# hv_control.net
KiCad netlist of a schematic drawn in Altium Designer
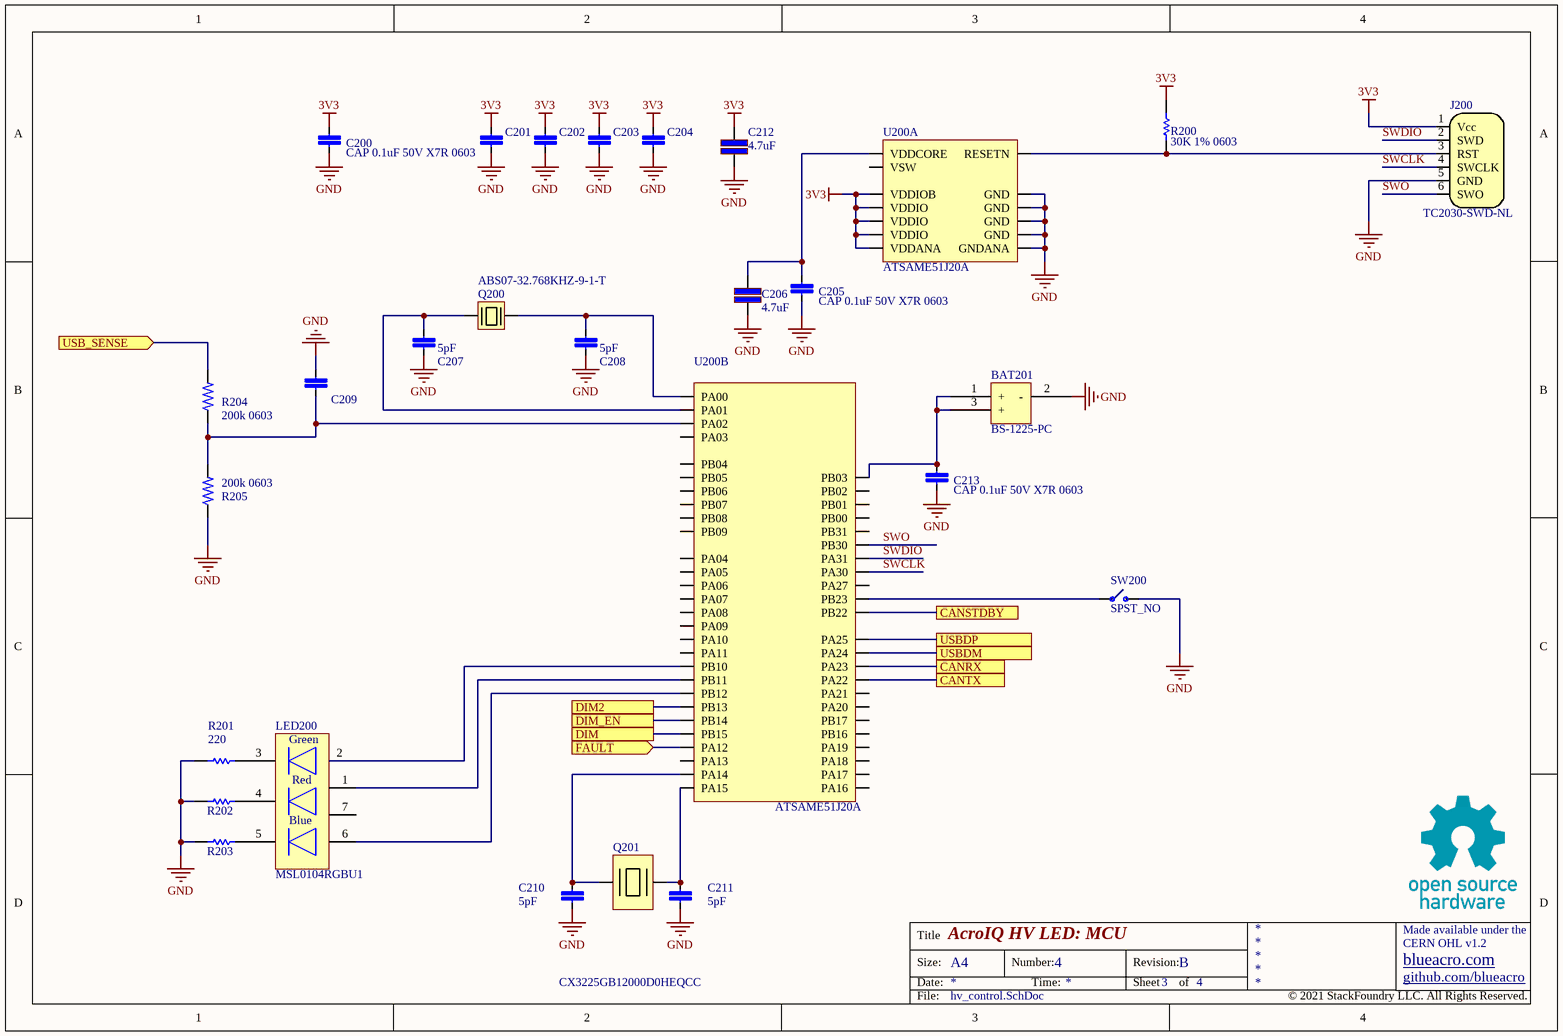
[diagram p0: hv_control.SchDoc]

(export (version "E")
  (design (tool "Eeschema 10.0.6"))
  (components
    (comp (ref "BAT201")
      (value "BS-1225-PC")
      (footprint "BS-1225-PC-Footprint-1")
      (description "BATTERY HOLDER COIN PC PIN")
      (libsource (lib "StackFoundry LLC") (part "BS-1225-PC"))
    )
    (comp (ref "C200")
      (value "CAP 0.1uF 50V X7R 0603")
      (footprint "FP-CL10-IPC_B")
      (description "Cap Ceramic 0.1uF 50V X7R 20% SMD 0603 125C Paper T/R")
      (libsource (lib "StackFoundry LLC") (part "C-EU"))
    )
    (comp (ref "C201")
      (value "CAP 0.1uF 50V X7R 0603")
      (footprint "FP-CL10-IPC_B")
      (description "Cap Ceramic 0.1uF 50V X7R 20% SMD 0603 125C Paper T/R")
      (libsource (lib "StackFoundry LLC") (part "C-EU"))
    )
    (comp (ref "C202")
      (value "CAP 0.1uF 50V X7R 0603")
      (footprint "FP-CL10-IPC_B")
      (description "Cap Ceramic 0.1uF 50V X7R 20% SMD 0603 125C Paper T/R")
      (libsource (lib "StackFoundry LLC") (part "C-EU"))
    )
    (comp (ref "C203")
      (value "CAP 0.1uF 50V X7R 0603")
      (footprint "FP-CL10-IPC_B")
      (description "Cap Ceramic 0.1uF 50V X7R 20% SMD 0603 125C Paper T/R")
      (libsource (lib "StackFoundry LLC") (part "C-EU"))
    )
    (comp (ref "C204")
      (value "CAP 0.1uF 50V X7R 0603")
      (footprint "FP-CL10-IPC_B")
      (description "Cap Ceramic 0.1uF 50V X7R 20% SMD 0603 125C Paper T/R")
      (libsource (lib "StackFoundry LLC") (part "C-EU"))
    )
    (comp (ref "C205")
      (value "CAP 0.1uF 50V X7R 0603")
      (footprint "FP-CL10-IPC_B")
      (description "Cap Ceramic 0.1uF 50V X7R 20% SMD 0603 125C Paper T/R")
      (libsource (lib "StackFoundry LLC") (part "C-EU"))
    )
    (comp (ref "C206")
      (value "4.7uF")
      (footprint "CAPC3225X20N")
      (description "CAP CER 4.7UF 50V X7R 1210")
      (fields (field (name "TOLERANCE") "10%") (field (name "VOLTAGE") "50V"))
      (libsource (lib "StackFoundry LLC") (part "4.7uF"))
    )
    (comp (ref "C207")
      (value "5pF")
      (footprint "FP-CL10-IPC_B")
      (description "CAP CER 5PF 50V C0G/NP0 0603")
      (libsource (lib "StackFoundry LLC") (part "C-EU"))
    )
    (comp (ref "C208")
      (value "5pF")
      (footprint "FP-CL10-IPC_B")
      (description "CAP CER 5PF 50V C0G/NP0 0603")
      (libsource (lib "StackFoundry LLC") (part "C-EU"))
    )
    (comp (ref "C209")
      (value "CAP 0.022uF 50V X7R 0603")
      (footprint "FP-CL10-IPC_B")
      (libsource (lib "StackFoundry LLC") (part "C-EU"))
    )
    (comp (ref "C210")
      (value "5pF")
      (footprint "FP-CL10-IPC_B")
      (description "CAP CER 5PF 50V C0G/NP0 0603")
      (libsource (lib "StackFoundry LLC") (part "C-EU"))
    )
    (comp (ref "C211")
      (value "5pF")
      (footprint "FP-CL10-IPC_B")
      (description "CAP CER 5PF 50V C0G/NP0 0603")
      (libsource (lib "StackFoundry LLC") (part "C-EU"))
    )
    (comp (ref "C212")
      (value "4.7uF")
      (footprint "CAPC3225X20N")
      (description "CAP CER 4.7UF 50V X7R 1210")
      (fields (field (name "TOLERANCE") "10%") (field (name "VOLTAGE") "50V"))
      (libsource (lib "StackFoundry LLC") (part "4.7uF"))
    )
    (comp (ref "C213")
      (value "CAP 0.1uF 50V X7R 0603")
      (footprint "FP-CL10-IPC_B")
      (description "Cap Ceramic 0.1uF 50V X7R 20% SMD 0603 125C Paper T/R")
      (libsource (lib "StackFoundry LLC") (part "C-EU"))
    )
    (comp (ref "J200")
      (value "TC2030-SWD-NL")
      (footprint "TC2030-MCP-NL")
      (description "Conector par ICD")
      (libsource (lib "StackFoundry LLC") (part "TC2030-SWD-NL"))
    )
    (comp (ref "LED200")
      (value "MSL0104RGBU1")
      (footprint "FP-MSL0104-MFG")
      (description "ROHM - MSL0104RGBU1 - LED ROT/GRÜN/BLAU 700/1200/400 MCD, 2709")
      (libsource (lib "StackFoundry LLC") (part "c1ae77389a615bb85b9424d60117df8"))
    )
    (comp (ref "Q200")
      (value "ABS07-32.768KHZ-9-1-T")
      (footprint "ABS07-32.768KHZ-9-1-T-Footprint-1")
      (description "CRYSTAL 32.768KHZ 9PF SMD")
      (fields (field (name "TOLERANCE") "10ppm"))
      (libsource (lib "StackFoundry LLC") (part "ABS07-32.768KHZ-9-1-T"))
    )
    (comp (ref "Q201")
      (value "CX3225GB12000D0HEQCC")
      (footprint "CX3225GB12000D0HEQCC-Footprint-1")
      (description "Crystal 12MHz ±20ppm (Tol) ±30ppm (Stability) 8pF FUND 250Ohm 4-Pin SMD T/R")
      (fields (field (name "TOLERANCE") "20ppm"))
      (libsource (lib "StackFoundry LLC") (part "CX3225GB12000D0HEQCC"))
    )
    (comp (ref "R200")
      (value "30K 1% 0603")
      (footprint "RESC1608-IPC-NL")
      (description "YAGEO - RC0603FR-0730KL - RES, THICK FILM, 30K, 1%, 0.1W, 0603, REEL")
      (fields (field (name "TOLERANCE") "1%"))
      (libsource (lib "StackFoundry LLC") (part "30K 1% 0603"))
    )
    (comp (ref "R201")
      (value "220")
      (footprint "RESC1608-IPC-NL")
      (fields (field (name "TOLERANCE") "5%"))
      (libsource (lib "StackFoundry LLC") (part "RES-2"))
    )
    (comp (ref "R202")
      (value "220R 0603 5%")
      (footprint "RESC1608-IPC-NL")
      (fields (field (name "TOLERANCE") "5%"))
      (libsource (lib "StackFoundry LLC") (part "RES-2"))
    )
    (comp (ref "R203")
      (value "220R 0603 5%")
      (footprint "RESC1608-IPC-NL")
      (fields (field (name "TOLERANCE") "5%"))
      (libsource (lib "StackFoundry LLC") (part "RES-2"))
    )
    (comp (ref "R204")
      (value "200k 0603")
      (footprint "RESC1608-IPC-NL")
      (description "Thick Film Resistors - SMD 200K OHM 5%")
      (libsource (lib "StackFoundry LLC") (part "R-US"))
    )
    (comp (ref "R205")
      (value "200k 0603")
      (footprint "RESC1608-IPC-NL")
      (description "Thick Film Resistors - SMD 200K OHM 5%")
      (libsource (lib "StackFoundry LLC") (part "R-US"))
    )
    (comp (ref "SW200")
      (value "SPST_NO")
      (footprint "TE_1825027-8")
      (libsource (lib "StackFoundry LLC") (part "SPST_NO"))
    )
    (comp (ref "U200")
      (value "ATSAME51J20A")
      (footprint "LQFP64")
      (description "IC MCU 32BIT 1MB FLASH 64TQFP")
      (libsource (lib "StackFoundry LLC") (part "ATSAME51J19A"))
    )
  )
  (nets
    (net (code "1") (name "/CANRX") (class "Default")
      (node (ref "U200") (pin "44") (pinfunction "PA23_44") (pintype "passive"))
    )
    (net (code "2") (name "/CANSTDBY") (class "Default")
      (node (ref "U200") (pin "49") (pinfunction "PB22_49") (pintype "passive"))
    )
    (net (code "3") (name "/CANTX") (class "Default")
      (node (ref "U200") (pin "43") (pinfunction "PA22_43") (pintype "passive"))
    )
    (net (code "4") (name "/DIM") (class "Default")
      (node (ref "U200") (pin "28") (pinfunction "PB15_28") (pintype "passive"))
    )
    (net (code "5") (name "/DIM2") (class "Default")
      (node (ref "U200") (pin "26") (pinfunction "PB13_26") (pintype "passive"))
    )
    (net (code "6") (name "/DIM_EN") (class "Default")
      (node (ref "U200") (pin "27") (pinfunction "PB14_27") (pintype "passive"))
    )
    (net (code "7") (name "/FAULT") (class "Default")
      (node (ref "U200") (pin "29") (pinfunction "PA12_29") (pintype "passive"))
    )
    (net (code "8") (name "/SWCLK") (class "Default")
      (node (ref "J200") (pin "4") (pinfunction "SWCLK_4") (pintype "passive"))
      (node (ref "U200") (pin "57") (pinfunction "PA30_57") (pintype "passive"))
    )
    (net (code "9") (name "/SWDIO") (class "Default")
      (node (ref "J200") (pin "2") (pinfunction "SWD_2") (pintype "passive"))
      (node (ref "U200") (pin "58") (pinfunction "PA31_58") (pintype "passive"))
    )
    (net (code "10") (name "/SWO") (class "Default")
      (node (ref "J200") (pin "6") (pinfunction "SWO_6") (pintype "passive"))
      (node (ref "U200") (pin "59") (pinfunction "PB30_59") (pintype "passive"))
    )
    (net (code "11") (name "/USBDM") (class "Default")
      (node (ref "U200") (pin "45") (pinfunction "PA24_45") (pintype "passive"))
    )
    (net (code "12") (name "/USBDP") (class "Default")
      (node (ref "U200") (pin "46") (pinfunction "PA25_46") (pintype "passive"))
    )
    (net (code "13") (name "/USB_SENSE") (class "Default")
      (node (ref "R204") (pin "2") (pinfunction "2_2") (pintype "passive"))
    )
    (net (code "14") (name "3V3") (class "Default")
      (node (ref "C200") (pin "1") (pinfunction "1_1") (pintype "passive"))
      (node (ref "C201") (pin "1") (pinfunction "1_1") (pintype "passive"))
      (node (ref "C202") (pin "1") (pinfunction "1_1") (pintype "passive"))
      (node (ref "C203") (pin "1") (pinfunction "1_1") (pintype "passive"))
      (node (ref "C204") (pin "1") (pinfunction "1_1") (pintype "passive"))
      (node (ref "C212") (pin "2") (pintype "passive"))
      (node (ref "J200") (pin "1") (pinfunction "Vcc_1") (pintype "passive"))
      (node (ref "R200") (pin "2") (pinfunction "2_2") (pintype "passive"))
      (node (ref "U200") (pin "21") (pinfunction "VDDIOB_21") (pintype "passive"))
      (node (ref "U200") (pin "34") (pinfunction "VDDIO_34") (pintype "passive"))
      (node (ref "U200") (pin "48") (pinfunction "VDDIO_48") (pintype "passive"))
      (node (ref "U200") (pin "56") (pinfunction "VDDIO_56") (pintype "passive"))
      (node (ref "U200") (pin "8") (pinfunction "VDDANA_8") (pintype "passive"))
    )
    (net (code "15") (name "GND") (class "Default")
      (node (ref "BAT201") (pin "2") (pinfunction "-_2") (pintype "passive"))
      (node (ref "C200") (pin "2") (pinfunction "2_2") (pintype "passive"))
      (node (ref "C201") (pin "2") (pinfunction "2_2") (pintype "passive"))
      (node (ref "C202") (pin "2") (pinfunction "2_2") (pintype "passive"))
      (node (ref "C203") (pin "2") (pinfunction "2_2") (pintype "passive"))
      (node (ref "C204") (pin "2") (pinfunction "2_2") (pintype "passive"))
      (node (ref "C205") (pin "2") (pinfunction "2_2") (pintype "passive"))
      (node (ref "C206") (pin "1") (pintype "passive"))
      (node (ref "C207") (pin "2") (pinfunction "2_2") (pintype "passive"))
      (node (ref "C208") (pin "2") (pinfunction "2_2") (pintype "passive"))
      (node (ref "C209") (pin "1") (pinfunction "1_1") (pintype "passive"))
      (node (ref "C210") (pin "2") (pinfunction "2_2") (pintype "passive"))
      (node (ref "C211") (pin "2") (pinfunction "2_2") (pintype "passive"))
      (node (ref "C212") (pin "1") (pintype "passive"))
      (node (ref "C213") (pin "2") (pinfunction "2_2") (pintype "passive"))
      (node (ref "J200") (pin "5") (pinfunction "GND_5") (pintype "passive"))
      (node (ref "R201") (pin "1") (pinfunction "1_1") (pintype "passive"))
      (node (ref "R202") (pin "1") (pinfunction "1_1") (pintype "passive"))
      (node (ref "R203") (pin "1") (pinfunction "1_1") (pintype "passive"))
      (node (ref "R205") (pin "1") (pinfunction "1_1") (pintype "passive"))
      (node (ref "SW200") (pin "1") (pinfunction "1_1") (pintype "passive"))
      (node (ref "U200") (pin "22") (pinfunction "GND_22") (pintype "passive"))
      (node (ref "U200") (pin "33") (pinfunction "GND_33") (pintype "passive"))
      (node (ref "U200") (pin "47") (pinfunction "GND_47") (pintype "passive"))
      (node (ref "U200") (pin "54") (pinfunction "GND_54") (pintype "passive"))
      (node (ref "U200") (pin "7") (pinfunction "GNDANA_7") (pintype "passive"))
    )
    (net (code "16") (name "Net-(J200-RST)") (class "Default")
      (node (ref "J200") (pin "3") (pinfunction "RST_3") (pintype "passive"))
      (node (ref "R200") (pin "1") (pinfunction "1_1") (pintype "passive"))
      (node (ref "U200") (pin "52") (pinfunction "RESETN_52") (pintype "passive"))
    )
    (net (code "17") (name "Net-(LED200-B_A)") (class "Default")
      (node (ref "LED200") (pin "6") (pinfunction "B_A_6") (pintype "passive"))
      (node (ref "U200") (pin "25") (pinfunction "PB12_25") (pintype "passive"))
    )
    (net (code "18") (name "Net-(LED200-B_K)") (class "Default")
      (node (ref "LED200") (pin "5") (pinfunction "B_K_5") (pintype "passive"))
      (node (ref "R203") (pin "2") (pinfunction "2_2") (pintype "passive"))
    )
    (net (code "19") (name "Net-(LED200-G_A)") (class "Default")
      (node (ref "LED200") (pin "2") (pinfunction "G_A_2") (pintype "passive"))
      (node (ref "U200") (pin "23") (pinfunction "PB10_23") (pintype "passive"))
    )
    (net (code "20") (name "Net-(LED200-G_K)") (class "Default")
      (node (ref "LED200") (pin "3") (pinfunction "G_K_3") (pintype "passive"))
      (node (ref "R201") (pin "2") (pinfunction "2_2") (pintype "passive"))
    )
    (net (code "21") (name "Net-(LED200-R_K)") (class "Default")
      (node (ref "LED200") (pin "4") (pinfunction "R_K_4") (pintype "passive"))
      (node (ref "R202") (pin "2") (pinfunction "2_2") (pintype "passive"))
    )
    (net (code "22") (name "Net-(U200A-VDDCORE)") (class "Default")
      (node (ref "C205") (pin "1") (pinfunction "1_1") (pintype "passive"))
      (node (ref "C206") (pin "2") (pintype "passive"))
      (node (ref "U200") (pin "53") (pinfunction "VDDCORE_53") (pintype "passive"))
    )
    (net (code "23") (name "Net-(U200B-PA00)") (class "Default")
      (node (ref "C208") (pin "1") (pinfunction "1_1") (pintype "passive"))
      (node (ref "Q200") (pin "2") (pintype "passive"))
      (node (ref "U200") (pin "1") (pinfunction "PA00_1") (pintype "passive"))
    )
    (net (code "24") (name "Net-(U200B-PA01)") (class "Default")
      (node (ref "C207") (pin "1") (pinfunction "1_1") (pintype "passive"))
      (node (ref "Q200") (pin "1") (pintype "passive"))
      (node (ref "U200") (pin "2") (pinfunction "PA01_2") (pintype "passive"))
    )
    (net (code "25") (name "Net-(U200B-PA02)") (class "Default")
      (node (ref "C209") (pin "2") (pinfunction "2_2") (pintype "passive"))
      (node (ref "R204") (pin "1") (pinfunction "1_1") (pintype "passive"))
      (node (ref "R205") (pin "2") (pinfunction "2_2") (pintype "passive"))
      (node (ref "U200") (pin "3") (pinfunction "PA02_3") (pintype "passive"))
    )
    (net (code "26") (name "Net-(U200B-PA14)") (class "Default")
      (node (ref "C210") (pin "1") (pinfunction "1_1") (pintype "passive"))
      (node (ref "Q201") (pin "1") (pinfunction "1_1") (pintype "passive"))
      (node (ref "U200") (pin "31") (pinfunction "PA14_31") (pintype "passive"))
    )
    (net (code "27") (name "Net-(U200B-PA15)") (class "Default")
      (node (ref "C211") (pin "1") (pinfunction "1_1") (pintype "passive"))
      (node (ref "Q201") (pin "3") (pinfunction "3_3") (pintype "passive"))
      (node (ref "U200") (pin "32") (pinfunction "PA15_32") (pintype "passive"))
    )
    (net (code "28") (name "Net-(U200B-PB03)") (class "Default")
      (node (ref "BAT201") (pin "1") (pinfunction "+_1") (pintype "passive"))
      (node (ref "BAT201") (pin "3") (pinfunction "+_3") (pintype "passive"))
      (node (ref "C213") (pin "1") (pinfunction "1_1") (pintype "passive"))
      (node (ref "U200") (pin "64") (pinfunction "PB03_64") (pintype "passive"))
    )
    (net (code "29") (name "Net-(U200B-PB11)") (class "Default")
      (node (ref "LED200") (pin "1") (pinfunction "R_A_1") (pintype "passive"))
      (node (ref "U200") (pin "24") (pinfunction "PB11_24") (pintype "passive"))
    )
    (net (code "30") (name "Net-(U200B-PB23)") (class "Default")
      (node (ref "SW200") (pin "2") (pinfunction "2_2") (pintype "passive"))
      (node (ref "U200") (pin "50") (pinfunction "PB23_50") (pintype "passive"))
    )
    (net (code "31") (name "unconnected-(LED200-R_A-Pad7)") (class "Default")
      (node (ref "LED200") (pin "7") (pinfunction "R_A_7") (pintype "passive"))
    )
    (net (code "32") (name "unconnected-(U200A-VSW-Pad55)") (class "Default")
      (node (ref "U200") (pin "55") (pinfunction "VSW_55") (pintype "passive"))
    )
    (net (code "33") (name "unconnected-(U200B-PA03-Pad4)") (class "Default")
      (node (ref "U200") (pin "4") (pinfunction "PA03_4") (pintype "passive"))
    )
    (net (code "34") (name "unconnected-(U200B-PA04-Pad13)") (class "Default")
      (node (ref "U200") (pin "13") (pinfunction "PA04_13") (pintype "passive"))
    )
    (net (code "35") (name "unconnected-(U200B-PA05-Pad14)") (class "Default")
      (node (ref "U200") (pin "14") (pinfunction "PA05_14") (pintype "passive"))
    )
    (net (code "36") (name "unconnected-(U200B-PA06-Pad15)") (class "Default")
      (node (ref "U200") (pin "15") (pinfunction "PA06_15") (pintype "passive"))
    )
    (net (code "37") (name "unconnected-(U200B-PA07-Pad16)") (class "Default")
      (node (ref "U200") (pin "16") (pinfunction "PA07_16") (pintype "passive"))
    )
    (net (code "38") (name "unconnected-(U200B-PA08-Pad17)") (class "Default")
      (node (ref "U200") (pin "17") (pinfunction "PA08_17") (pintype "passive"))
    )
    (net (code "39") (name "unconnected-(U200B-PA09-Pad18)") (class "Default")
      (node (ref "U200") (pin "18") (pinfunction "PA09_18") (pintype "passive"))
    )
    (net (code "40") (name "unconnected-(U200B-PA10-Pad19)") (class "Default")
      (node (ref "U200") (pin "19") (pinfunction "PA10_19") (pintype "passive"))
    )
    (net (code "41") (name "unconnected-(U200B-PA11-Pad20)") (class "Default")
      (node (ref "U200") (pin "20") (pinfunction "PA11_20") (pintype "passive"))
    )
    (net (code "42") (name "unconnected-(U200B-PA13-Pad30)") (class "Default")
      (node (ref "U200") (pin "30") (pinfunction "PA13_30") (pintype "passive"))
    )
    (net (code "43") (name "unconnected-(U200B-PA16-Pad35)") (class "Default")
      (node (ref "U200") (pin "35") (pinfunction "PA16_35") (pintype "passive"))
    )
    (net (code "44") (name "unconnected-(U200B-PA17-Pad36)") (class "Default")
      (node (ref "U200") (pin "36") (pinfunction "PA17_36") (pintype "passive"))
    )
    (net (code "45") (name "unconnected-(U200B-PA18-Pad37)") (class "Default")
      (node (ref "U200") (pin "37") (pinfunction "PA18_37") (pintype "passive"))
    )
    (net (code "46") (name "unconnected-(U200B-PA19-Pad38)") (class "Default")
      (node (ref "U200") (pin "38") (pinfunction "PA19_38") (pintype "passive"))
    )
    (net (code "47") (name "unconnected-(U200B-PA20-Pad41)") (class "Default")
      (node (ref "U200") (pin "41") (pinfunction "PA20_41") (pintype "passive"))
    )
    (net (code "48") (name "unconnected-(U200B-PA21-Pad42)") (class "Default")
      (node (ref "U200") (pin "42") (pinfunction "PA21_42") (pintype "passive"))
    )
    (net (code "49") (name "unconnected-(U200B-PA27-Pad51)") (class "Default")
      (node (ref "U200") (pin "51") (pinfunction "PA27_51") (pintype "passive"))
    )
    (net (code "50") (name "unconnected-(U200B-PB00-Pad61)") (class "Default")
      (node (ref "U200") (pin "61") (pinfunction "PB00_61") (pintype "passive"))
    )
    (net (code "51") (name "unconnected-(U200B-PB01-Pad62)") (class "Default")
      (node (ref "U200") (pin "62") (pinfunction "PB01_62") (pintype "passive"))
    )
    (net (code "52") (name "unconnected-(U200B-PB02-Pad63)") (class "Default")
      (node (ref "U200") (pin "63") (pinfunction "PB02_63") (pintype "passive"))
    )
    (net (code "53") (name "unconnected-(U200B-PB04-Pad5)") (class "Default")
      (node (ref "U200") (pin "5") (pinfunction "PB04_5") (pintype "passive"))
    )
    (net (code "54") (name "unconnected-(U200B-PB05-Pad6)") (class "Default")
      (node (ref "U200") (pin "6") (pinfunction "PB05_6") (pintype "passive"))
    )
    (net (code "55") (name "unconnected-(U200B-PB06-Pad9)") (class "Default")
      (node (ref "U200") (pin "9") (pinfunction "PB06_9") (pintype "passive"))
    )
    (net (code "56") (name "unconnected-(U200B-PB07-Pad10)") (class "Default")
      (node (ref "U200") (pin "10") (pinfunction "PB07_10") (pintype "passive"))
    )
    (net (code "57") (name "unconnected-(U200B-PB08-Pad11)") (class "Default")
      (node (ref "U200") (pin "11") (pinfunction "PB08_11") (pintype "passive"))
    )
    (net (code "58") (name "unconnected-(U200B-PB09-Pad12)") (class "Default")
      (node (ref "U200") (pin "12") (pinfunction "PB09_12") (pintype "passive"))
    )
    (net (code "59") (name "unconnected-(U200B-PB16-Pad39)") (class "Default")
      (node (ref "U200") (pin "39") (pinfunction "PB16_39") (pintype "passive"))
    )
    (net (code "60") (name "unconnected-(U200B-PB17-Pad40)") (class "Default")
      (node (ref "U200") (pin "40") (pinfunction "PB17_40") (pintype "passive"))
    )
    (net (code "61") (name "unconnected-(U200B-PB31-Pad60)") (class "Default")
      (node (ref "U200") (pin "60") (pinfunction "PB31_60") (pintype "passive"))
    )
  )
)
